# Stepper-driver.net
KiCad netlist of a schematic drawn in Altium Designer
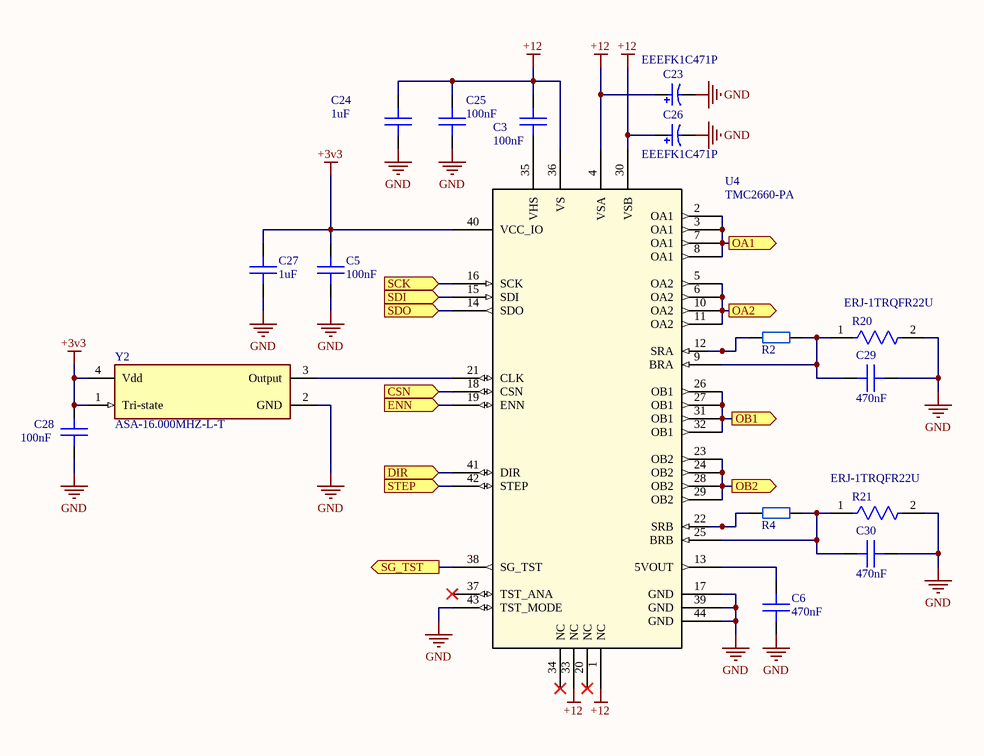
[diagram p0: Stepper-driver.SchDoc]

(export (version "E")
  (design (tool "Eeschema 10.0.6"))
  (components
    (comp (ref "C3")
      (value "100nF")
      (footprint "C0603 (1608)")
      (fields (field (name "Comment") "Cap SMD"))
      (libsource (lib "Moto Symbol Lib") (part "Cap SMD"))
    )
    (comp (ref "C5")
      (value "100nF")
      (footprint "C0603 (1608)")
      (fields (field (name "Comment") "Cap SMD"))
      (libsource (lib "Moto Symbol Lib") (part "Cap SMD"))
    )
    (comp (ref "C6")
      (value "470nF")
      (footprint "C0603 (1608)")
      (fields (field (name "Comment") "Cap SMD"))
      (libsource (lib "Moto Symbol Lib") (part "Cap SMD"))
    )
    (comp (ref "C23")
      (value "EEEFK1C471P")
      (footprint "PNSC-FK-V-F_V")
      (fields (field (name "MANUFACTURER") "Panasonic"))
      (libsource (lib "Altium Content Vault") (part "CAP-P-2"))
    )
    (comp (ref "C24")
      (value "1uF")
      (footprint "C0603 (1608)")
      (fields (field (name "Comment") "Cap SMD"))
      (libsource (lib "Moto Symbol Lib") (part "Cap SMD"))
    )
    (comp (ref "C25")
      (value "100nF")
      (footprint "C0603 (1608)")
      (fields (field (name "Comment") "Cap SMD"))
      (libsource (lib "Moto Symbol Lib") (part "Cap SMD"))
    )
    (comp (ref "C26")
      (value "EEEFK1C471P")
      (footprint "PNSC-FK-V-F_V")
      (fields (field (name "MANUFACTURER") "Panasonic"))
      (libsource (lib "Altium Content Vault") (part "CAP-P-2"))
    )
    (comp (ref "C27")
      (value "1uF")
      (footprint "C0603 (1608)")
      (fields (field (name "Comment") "Cap SMD"))
      (libsource (lib "Moto Symbol Lib") (part "Cap SMD"))
    )
    (comp (ref "C28")
      (value "100nF")
      (footprint "C0603 (1608)")
      (fields (field (name "Comment") "Cap SMD"))
      (libsource (lib "Moto Symbol Lib") (part "Cap SMD"))
    )
    (comp (ref "C29")
      (value "470nF")
      (footprint "C0603 (1608)")
      (fields (field (name "Comment") "Cap SMD"))
      (libsource (lib "Moto Symbol Lib") (part "Cap SMD"))
    )
    (comp (ref "C30")
      (value "470nF")
      (footprint "C0603 (1608)")
      (fields (field (name "Comment") "Cap SMD"))
      (libsource (lib "Moto Symbol Lib") (part "Cap SMD"))
    )
    (comp (ref "R2")
      (value "Res")
      (footprint "R0603 (1608)")
      (libsource (lib "Moto Symbol Lib") (part "Resistor EU"))
    )
    (comp (ref "R4")
      (value "Res")
      (footprint "R0603 (1608)")
      (libsource (lib "Moto Symbol Lib") (part "Resistor EU"))
    )
    (comp (ref "R20")
      (value "ERJ-1TRQFR22U")
      (footprint "FP-ERJ1TR-MFG")
      (description "RES 0.22 OHM 1% 1W 2512")
      (fields
        (field (name "TOLERANCE") "1%")
        (field (name "OCTOPART") "https://octopart.com/erj1trqfr22u-panasonic-10566390")
      )
      (libsource (lib "Altium Content Vault") (part "1029c3af85768c4190bb7ad29bc67b5"))
    )
    (comp (ref "R21")
      (value "ERJ-1TRQFR22U")
      (footprint "FP-ERJ1TR-MFG")
      (description "RES 0.22 OHM 1% 1W 2512")
      (fields
        (field (name "TOLERANCE") "1%")
        (field (name "OCTOPART") "https://octopart.com/erj1trqfr22u-panasonic-10566390")
      )
      (libsource (lib "Altium Content Vault") (part "1029c3af85768c4190bb7ad29bc67b5"))
    )
    (comp (ref "U4")
      (value "TMC2660-PA")
      (footprint "LQFP44_12X12_TRI-M")
      (description "No Description Available")
      (fields (field (name "COPYRIGHT") "Copyright (C) 2016 Accelerated Designs. All rights reserved"))
      (libsource (lib "Moto Symbol Lib") (part "TMC2660-PA"))
    )
    (comp (ref "Y2")
      (value "ASA-16.000MHZ-L-T")
      (footprint "FP-ASA-MFG")
      (description "XTAL OSC XO 16.0000MHZ HCMOS SMD")
      (fields
        (field (name "OCTOPART") "https://octopart.com/asa-16.000mhz-l-t-abracon-21707822")
        (field (name "MANUFACTURER") "Abracon")
      )
      (libsource (lib "Altium Content Vault") (part "7c953fa1d91b086b7cda9813af2bec8"))
    )
  )
  (nets
    (net (code "1") (name "+3v3") (class "Default")
      (node (ref "C27") (pin "2") (pinfunction "2_2") (pintype "power_in"))
      (node (ref "C28") (pin "2") (pinfunction "2_2") (pintype "power_in"))
      (node (ref "C5") (pin "2") (pinfunction "2_2") (pintype "power_in"))
      (node (ref "U4") (pin "40") (pinfunction "VCC_IO_40") (pintype "power_in"))
      (node (ref "Y2") (pin "1") (pinfunction "Tri-state_1") (pintype "input"))
      (node (ref "Y2") (pin "4") (pinfunction "Vdd_4") (pintype "power_in"))
    )
    (net (code "2") (name "+12") (class "Default")
      (node (ref "C23") (pin "1") (pinfunction "1_1") (pintype "passive"))
      (node (ref "C24") (pin "1") (pinfunction "1_1") (pintype "power_in"))
      (node (ref "C25") (pin "1") (pinfunction "1_1") (pintype "power_in"))
      (node (ref "C26") (pin "1") (pinfunction "1_1") (pintype "passive"))
      (node (ref "C3") (pin "1") (pinfunction "1_1") (pintype "power_in"))
      (node (ref "U4") (pin "1") (pinfunction "NC_1") (pintype "passive"))
      (node (ref "U4") (pin "30") (pinfunction "VSB_30") (pintype "power_in"))
      (node (ref "U4") (pin "33") (pinfunction "NC_33") (pintype "passive"))
      (node (ref "U4") (pin "36") (pinfunction "VS_36") (pintype "power_in"))
      (node (ref "U4") (pin "4") (pinfunction "VSA_4") (pintype "power_in"))
    )
    (net (code "3") (name "/CSN") (class "Default")
      (node (ref "U4") (pin "18") (pinfunction "CSN_18") (pintype "bidirectional"))
    )
    (net (code "4") (name "/DIR") (class "Default")
      (node (ref "U4") (pin "41") (pinfunction "DIR_41") (pintype "bidirectional"))
    )
    (net (code "5") (name "/ENN") (class "Default")
      (node (ref "U4") (pin "19") (pinfunction "ENN_19") (pintype "bidirectional"))
    )
    (net (code "6") (name "/OA1") (class "Default")
      (node (ref "U4") (pin "2") (pinfunction "OA1_2") (pintype "output"))
      (node (ref "U4") (pin "3") (pinfunction "OA1_3") (pintype "output"))
      (node (ref "U4") (pin "7") (pinfunction "OA1_7") (pintype "output"))
      (node (ref "U4") (pin "8") (pinfunction "OA1_8") (pintype "output"))
    )
    (net (code "7") (name "/OA2") (class "Default")
      (node (ref "U4") (pin "10") (pinfunction "OA2_10") (pintype "output"))
      (node (ref "U4") (pin "11") (pinfunction "OA2_11") (pintype "output"))
      (node (ref "U4") (pin "5") (pinfunction "OA2_5") (pintype "output"))
      (node (ref "U4") (pin "6") (pinfunction "OA2_6") (pintype "output"))
    )
    (net (code "8") (name "/OB1") (class "Default")
      (node (ref "U4") (pin "26") (pinfunction "OB1_26") (pintype "output"))
      (node (ref "U4") (pin "27") (pinfunction "OB1_27") (pintype "output"))
      (node (ref "U4") (pin "31") (pinfunction "OB1_31") (pintype "output"))
      (node (ref "U4") (pin "32") (pinfunction "OB1_32") (pintype "output"))
    )
    (net (code "9") (name "/OB2") (class "Default")
      (node (ref "U4") (pin "23") (pinfunction "OB2_23") (pintype "output"))
      (node (ref "U4") (pin "24") (pinfunction "OB2_24") (pintype "output"))
      (node (ref "U4") (pin "28") (pinfunction "OB2_28") (pintype "output"))
      (node (ref "U4") (pin "29") (pinfunction "OB2_29") (pintype "output"))
    )
    (net (code "10") (name "/SCK") (class "Default")
      (node (ref "U4") (pin "16") (pinfunction "SCK_16") (pintype "input"))
    )
    (net (code "11") (name "/SDI") (class "Default")
      (node (ref "U4") (pin "15") (pinfunction "SDI_15") (pintype "input"))
    )
    (net (code "12") (name "/SDO") (class "Default")
      (node (ref "U4") (pin "14") (pinfunction "SDO_14") (pintype "output"))
    )
    (net (code "13") (name "/SG_TST") (class "Default")
      (node (ref "U4") (pin "38") (pinfunction "SG_TST_38") (pintype "output"))
    )
    (net (code "14") (name "/STEP") (class "Default")
      (node (ref "U4") (pin "42") (pinfunction "STEP_42") (pintype "bidirectional"))
    )
    (net (code "15") (name "GND") (class "Default")
      (node (ref "C23") (pin "2") (pinfunction "2_2") (pintype "passive"))
      (node (ref "C24") (pin "2") (pinfunction "2_2") (pintype "power_in"))
      (node (ref "C25") (pin "2") (pinfunction "2_2") (pintype "power_in"))
      (node (ref "C26") (pin "2") (pinfunction "2_2") (pintype "passive"))
      (node (ref "C27") (pin "1") (pinfunction "1_1") (pintype "power_in"))
      (node (ref "C28") (pin "1") (pinfunction "1_1") (pintype "power_in"))
      (node (ref "C29") (pin "1") (pinfunction "1_1") (pintype "power_in"))
      (node (ref "C30") (pin "1") (pinfunction "1_1") (pintype "power_in"))
      (node (ref "C5") (pin "1") (pinfunction "1_1") (pintype "power_in"))
      (node (ref "C6") (pin "1") (pinfunction "1_1") (pintype "power_in"))
      (node (ref "R20") (pin "2") (pinfunction "2_2") (pintype "passive"))
      (node (ref "R21") (pin "2") (pinfunction "2_2") (pintype "passive"))
      (node (ref "U4") (pin "17") (pinfunction "GND_17") (pintype "power_in"))
      (node (ref "U4") (pin "39") (pinfunction "GND_39") (pintype "power_in"))
      (node (ref "U4") (pin "43") (pinfunction "TST_MODE_43") (pintype "bidirectional"))
      (node (ref "U4") (pin "44") (pinfunction "GND_44") (pintype "power_in"))
      (node (ref "Y2") (pin "2") (pinfunction "GND_2") (pintype "power_in"))
    )
    (net (code "16") (name "Net-(U4-5VOUT)") (class "Default")
      (node (ref "C6") (pin "2") (pinfunction "2_2") (pintype "power_in"))
      (node (ref "U4") (pin "13") (pinfunction "5VOUT_13") (pintype "output"))
    )
    (net (code "17") (name "Net-(U4-BRA)") (class "Default")
      (node (ref "C29") (pin "2") (pinfunction "2_2") (pintype "power_in"))
      (node (ref "R2") (pin "2") (pinfunction "2_2") (pintype "power_in"))
      (node (ref "R20") (pin "1") (pinfunction "1_1") (pintype "passive"))
      (node (ref "U4") (pin "9") (pinfunction "BRA_9") (pintype "input"))
    )
    (net (code "18") (name "Net-(U4-BRB)") (class "Default")
      (node (ref "C30") (pin "2") (pinfunction "2_2") (pintype "power_in"))
      (node (ref "R21") (pin "1") (pinfunction "1_1") (pintype "passive"))
      (node (ref "R4") (pin "2") (pinfunction "2_2") (pintype "power_in"))
      (node (ref "U4") (pin "25") (pinfunction "BRB_25") (pintype "input"))
    )
    (net (code "19") (name "Net-(U4-CLK)") (class "Default")
      (node (ref "U4") (pin "21") (pinfunction "CLK_21") (pintype "bidirectional"))
      (node (ref "Y2") (pin "3") (pinfunction "Output_3") (pintype "passive"))
    )
    (net (code "20") (name "Net-(U4-SRA)") (class "Default")
      (node (ref "R2") (pin "1") (pinfunction "1_1") (pintype "power_in"))
      (node (ref "U4") (pin "12") (pinfunction "SRA_12") (pintype "input"))
    )
    (net (code "21") (name "Net-(U4-SRB)") (class "Default")
      (node (ref "R4") (pin "1") (pinfunction "1_1") (pintype "power_in"))
      (node (ref "U4") (pin "22") (pinfunction "SRB_22") (pintype "input"))
    )
    (net (code "22") (name "Net-(U4-VHS)") (class "Default")
      (node (ref "C3") (pin "2") (pinfunction "2_2") (pintype "power_in"))
      (node (ref "U4") (pin "35") (pinfunction "VHS_35") (pintype "power_in"))
    )
    (net (code "23") (name "unconnected-(U4-NC-Pad20)") (class "Default")
      (node (ref "U4") (pin "20") (pinfunction "NC_20") (pintype "passive+no_connect"))
    )
    (net (code "24") (name "unconnected-(U4-NC-Pad34)") (class "Default")
      (node (ref "U4") (pin "34") (pinfunction "NC_34") (pintype "passive+no_connect"))
    )
    (net (code "25") (name "unconnected-(U4-TST_ANA-Pad37)") (class "Default")
      (node (ref "U4") (pin "37") (pinfunction "TST_ANA_37") (pintype "bidirectional+no_connect"))
    )
  )
)
